# solenoid.net
KiCad netlist of a schematic drawn in Altium Designer
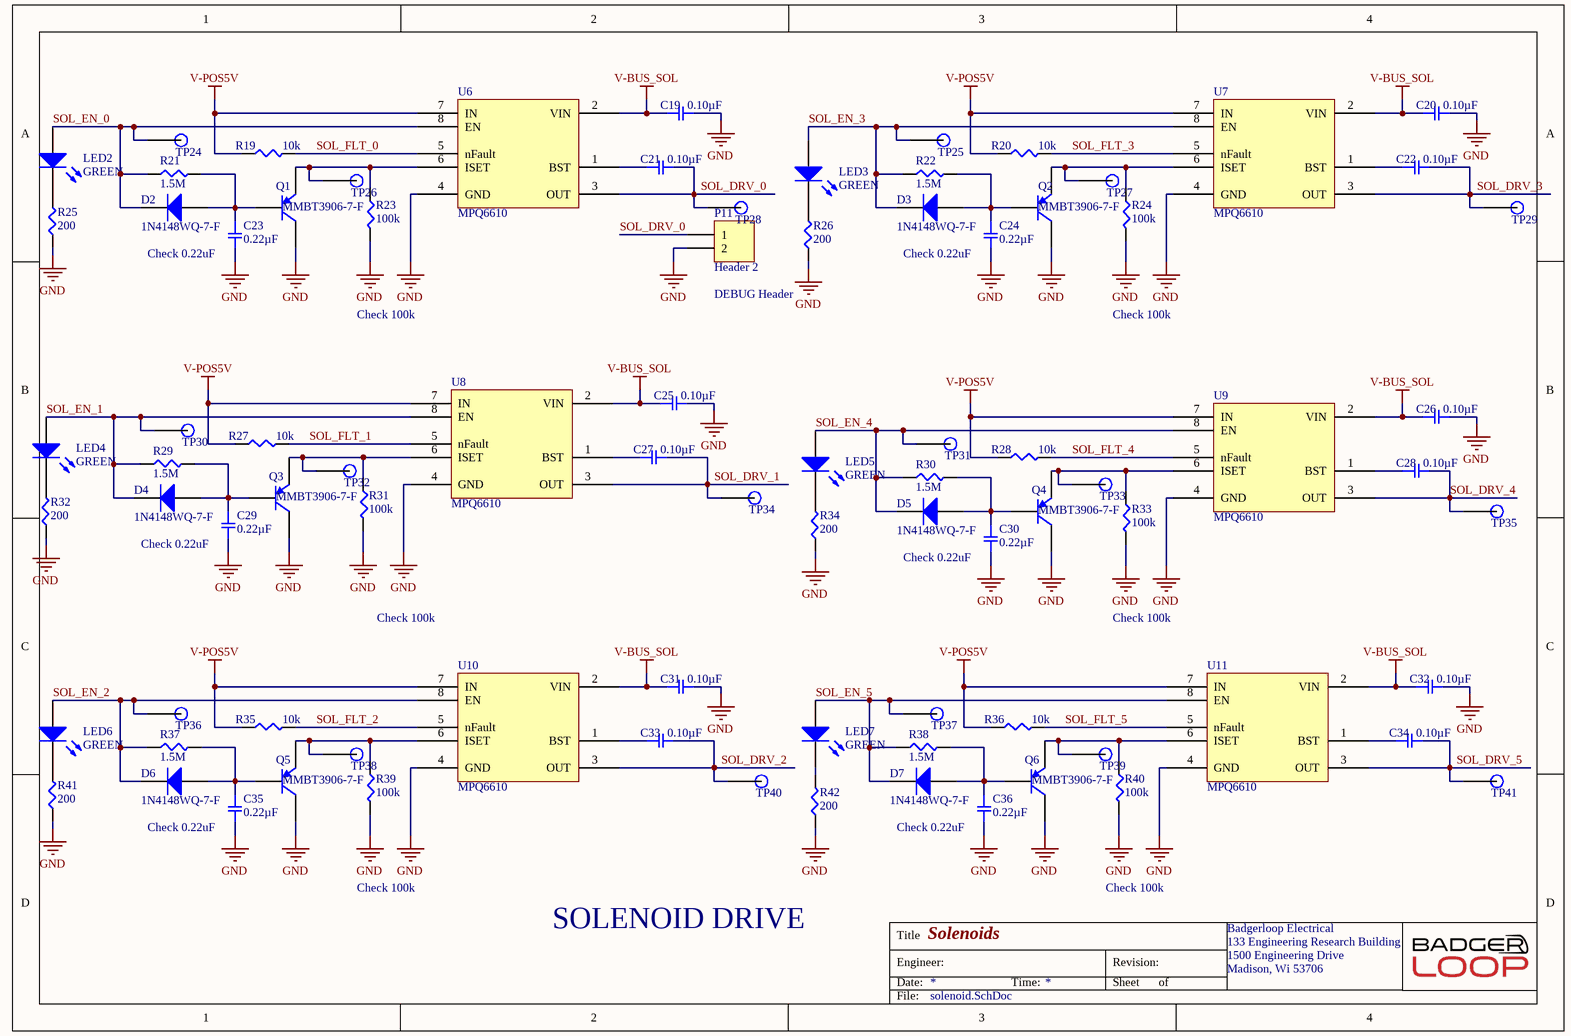
[diagram p0: solenoid.SchDoc]

(export (version "E")
  (design (tool "Eeschema 10.0.6"))
  (components
    (comp (ref "C19")
      (value "0.10µF")
      (footprint "SMD-0805C")
      (description "CAP CER 0.1UF 10V U2J 0805")
      (fields
        (field (name "DIGI-KEY PART NUMBER") "490-11592-1-ND")
        (field (name "PART NUMBER") "GRM21B7U1A104JA01L")
      )
      (libsource (lib "capacitors") (part "GRM21B7U1A104JA01L"))
    )
    (comp (ref "C20")
      (value "0.10µF")
      (footprint "SMD-0805C")
      (description "CAP CER 0.1UF 10V U2J 0805")
      (fields
        (field (name "DIGI-KEY PART NUMBER") "490-11592-1-ND")
        (field (name "PART NUMBER") "GRM21B7U1A104JA01L")
      )
      (libsource (lib "capacitors") (part "GRM21B7U1A104JA01L"))
    )
    (comp (ref "C21")
      (value "0.10µF")
      (footprint "SMD-0805C")
      (description "CAP CER 0.1UF 10V U2J 0805")
      (fields
        (field (name "DIGI-KEY PART NUMBER") "490-11592-1-ND")
        (field (name "PART NUMBER") "GRM21B7U1A104JA01L")
      )
      (libsource (lib "capacitors") (part "GRM21B7U1A104JA01L"))
    )
    (comp (ref "C22")
      (value "0.10µF")
      (footprint "SMD-0805C")
      (description "CAP CER 0.1UF 10V U2J 0805")
      (fields
        (field (name "DIGI-KEY PART NUMBER") "490-11592-1-ND")
        (field (name "PART NUMBER") "GRM21B7U1A104JA01L")
      )
      (libsource (lib "capacitors") (part "GRM21B7U1A104JA01L"))
    )
    (comp (ref "C23")
      (value "0.22µF")
      (footprint "SMD-0805C")
      (description "CAP CER 0.22UF 10V X7R 0805")
      (fields
        (field (name "DIGI-KEY PART NUMBER") "490-4432-1-ND")
        (field (name "PART NUMBER") "LLA215R71A224MA14L")
      )
      (libsource (lib "capacitors") (part "LLA215R71A224MA14L"))
    )
    (comp (ref "C24")
      (value "0.22µF")
      (footprint "SMD-0805C")
      (description "CAP CER 0.22UF 10V X7R 0805")
      (fields
        (field (name "DIGI-KEY PART NUMBER") "490-4432-1-ND")
        (field (name "PART NUMBER") "LLA215R71A224MA14L")
      )
      (libsource (lib "capacitors") (part "LLA215R71A224MA14L"))
    )
    (comp (ref "C25")
      (value "0.10µF")
      (footprint "SMD-0805C")
      (description "CAP CER 0.1UF 10V U2J 0805")
      (fields
        (field (name "DIGI-KEY PART NUMBER") "490-11592-1-ND")
        (field (name "PART NUMBER") "GRM21B7U1A104JA01L")
      )
      (libsource (lib "capacitors") (part "GRM21B7U1A104JA01L"))
    )
    (comp (ref "C26")
      (value "0.10µF")
      (footprint "SMD-0805C")
      (description "CAP CER 0.1UF 10V U2J 0805")
      (fields
        (field (name "DIGI-KEY PART NUMBER") "490-11592-1-ND")
        (field (name "PART NUMBER") "GRM21B7U1A104JA01L")
      )
      (libsource (lib "capacitors") (part "GRM21B7U1A104JA01L"))
    )
    (comp (ref "C27")
      (value "0.10µF")
      (footprint "SMD-0805C")
      (description "CAP CER 0.1UF 10V U2J 0805")
      (fields
        (field (name "DIGI-KEY PART NUMBER") "490-11592-1-ND")
        (field (name "PART NUMBER") "GRM21B7U1A104JA01L")
      )
      (libsource (lib "capacitors") (part "GRM21B7U1A104JA01L"))
    )
    (comp (ref "C28")
      (value "0.10µF")
      (footprint "SMD-0805C")
      (description "CAP CER 0.1UF 10V U2J 0805")
      (fields
        (field (name "DIGI-KEY PART NUMBER") "490-11592-1-ND")
        (field (name "PART NUMBER") "GRM21B7U1A104JA01L")
      )
      (libsource (lib "capacitors") (part "GRM21B7U1A104JA01L"))
    )
    (comp (ref "C29")
      (value "0.22µF")
      (footprint "SMD-0805C")
      (description "CAP CER 0.22UF 10V X7R 0805")
      (fields
        (field (name "DIGI-KEY PART NUMBER") "490-4432-1-ND")
        (field (name "PART NUMBER") "LLA215R71A224MA14L")
      )
      (libsource (lib "capacitors") (part "LLA215R71A224MA14L"))
    )
    (comp (ref "C30")
      (value "0.22µF")
      (footprint "SMD-0805C")
      (description "CAP CER 0.22UF 10V X7R 0805")
      (fields
        (field (name "DIGI-KEY PART NUMBER") "490-4432-1-ND")
        (field (name "PART NUMBER") "LLA215R71A224MA14L")
      )
      (libsource (lib "capacitors") (part "LLA215R71A224MA14L"))
    )
    (comp (ref "C31")
      (value "0.10µF")
      (footprint "SMD-0805C")
      (description "CAP CER 0.1UF 10V U2J 0805")
      (fields
        (field (name "DIGI-KEY PART NUMBER") "490-11592-1-ND")
        (field (name "PART NUMBER") "GRM21B7U1A104JA01L")
      )
      (libsource (lib "capacitors") (part "GRM21B7U1A104JA01L"))
    )
    (comp (ref "C32")
      (value "0.10µF")
      (footprint "SMD-0805C")
      (description "CAP CER 0.1UF 10V U2J 0805")
      (fields
        (field (name "DIGI-KEY PART NUMBER") "490-11592-1-ND")
        (field (name "PART NUMBER") "GRM21B7U1A104JA01L")
      )
      (libsource (lib "capacitors") (part "GRM21B7U1A104JA01L"))
    )
    (comp (ref "C33")
      (value "0.10µF")
      (footprint "SMD-0805C")
      (description "CAP CER 0.1UF 10V U2J 0805")
      (fields
        (field (name "DIGI-KEY PART NUMBER") "490-11592-1-ND")
        (field (name "PART NUMBER") "GRM21B7U1A104JA01L")
      )
      (libsource (lib "capacitors") (part "GRM21B7U1A104JA01L"))
    )
    (comp (ref "C34")
      (value "0.10µF")
      (footprint "SMD-0805C")
      (description "CAP CER 0.1UF 10V U2J 0805")
      (fields
        (field (name "DIGI-KEY PART NUMBER") "490-11592-1-ND")
        (field (name "PART NUMBER") "GRM21B7U1A104JA01L")
      )
      (libsource (lib "capacitors") (part "GRM21B7U1A104JA01L"))
    )
    (comp (ref "C35")
      (value "0.22µF")
      (footprint "SMD-0805C")
      (description "CAP CER 0.22UF 10V X7R 0805")
      (fields
        (field (name "DIGI-KEY PART NUMBER") "490-4432-1-ND")
        (field (name "PART NUMBER") "LLA215R71A224MA14L")
      )
      (libsource (lib "capacitors") (part "LLA215R71A224MA14L"))
    )
    (comp (ref "C36")
      (value "0.22µF")
      (footprint "SMD-0805C")
      (description "CAP CER 0.22UF 10V X7R 0805")
      (fields
        (field (name "DIGI-KEY PART NUMBER") "490-4432-1-ND")
        (field (name "PART NUMBER") "LLA215R71A224MA14L")
      )
      (libsource (lib "capacitors") (part "LLA215R71A224MA14L"))
    )
    (comp (ref "D2")
      (value "1N4148WQ-7-F")
      (footprint "INDM3838X18N")
      (description "Diodes - General Purpose, Power, Switching SMT Fast Switching Diode")
      (fields (field (name "MANUFACTURER") "Diodes Inc."))
      (libsource (lib "misc") (part "1N4148WQ-7-F"))
    )
    (comp (ref "D3")
      (value "1N4148WQ-7-F")
      (footprint "INDM3838X18N")
      (description "Diodes - General Purpose, Power, Switching SMT Fast Switching Diode")
      (fields (field (name "MANUFACTURER") "Diodes Inc."))
      (libsource (lib "misc") (part "1N4148WQ-7-F"))
    )
    (comp (ref "D4")
      (value "1N4148WQ-7-F")
      (footprint "INDM3838X18N")
      (description "Diodes - General Purpose, Power, Switching SMT Fast Switching Diode")
      (fields (field (name "MANUFACTURER") "Diodes Inc."))
      (libsource (lib "misc") (part "1N4148WQ-7-F"))
    )
    (comp (ref "D5")
      (value "1N4148WQ-7-F")
      (footprint "INDM3838X18N")
      (description "Diodes - General Purpose, Power, Switching SMT Fast Switching Diode")
      (fields (field (name "MANUFACTURER") "Diodes Inc."))
      (libsource (lib "misc") (part "1N4148WQ-7-F"))
    )
    (comp (ref "D6")
      (value "1N4148WQ-7-F")
      (footprint "INDM3838X18N")
      (description "Diodes - General Purpose, Power, Switching SMT Fast Switching Diode")
      (fields (field (name "MANUFACTURER") "Diodes Inc."))
      (libsource (lib "misc") (part "1N4148WQ-7-F"))
    )
    (comp (ref "D7")
      (value "1N4148WQ-7-F")
      (footprint "INDM3838X18N")
      (description "Diodes - General Purpose, Power, Switching SMT Fast Switching Diode")
      (fields (field (name "MANUFACTURER") "Diodes Inc."))
      (libsource (lib "misc") (part "1N4148WQ-7-F"))
    )
    (comp (ref "LED2")
      (value "GREEN")
      (footprint "LED 0603 GREEN")
      (fields (field (name "MANUFACTURER") "Lite-On Inc."))
      (libsource (lib "misc") (part "LED GREEN 0603"))
    )
    (comp (ref "LED3")
      (value "GREEN")
      (footprint "LED 0603 GREEN")
      (fields (field (name "MANUFACTURER") "Lite-On Inc."))
      (libsource (lib "misc") (part "LED GREEN 0603"))
    )
    (comp (ref "LED4")
      (value "GREEN")
      (footprint "LED 0603 GREEN")
      (fields (field (name "MANUFACTURER") "Lite-On Inc."))
      (libsource (lib "misc") (part "LED GREEN 0603"))
    )
    (comp (ref "LED5")
      (value "GREEN")
      (footprint "LED 0603 GREEN")
      (fields (field (name "MANUFACTURER") "Lite-On Inc."))
      (libsource (lib "misc") (part "LED GREEN 0603"))
    )
    (comp (ref "LED6")
      (value "GREEN")
      (footprint "LED 0603 GREEN")
      (fields (field (name "MANUFACTURER") "Lite-On Inc."))
      (libsource (lib "misc") (part "LED GREEN 0603"))
    )
    (comp (ref "LED7")
      (value "GREEN")
      (footprint "LED 0603 GREEN")
      (fields (field (name "MANUFACTURER") "Lite-On Inc."))
      (libsource (lib "misc") (part "LED GREEN 0603"))
    )
    (comp (ref "P11")
      (value "Header 2")
      (footprint "Pin Header 1x2 TH Pitch 2.54mm")
      (description "Header, 2-Pin")
      (fields (field (name "PUBLISHER") "Altium Limited"))
      (libsource (lib "connector") (part "Header 2"))
    )
    (comp (ref "Q1")
      (value "MMBT3906-7-F")
      (footprint "SOTFL103P240X110-3N")
      (fields (field (name "MANUFACTURER") "Diodes Zetex"))
      (libsource (lib "misc") (part "MMBT3906-7-F"))
    )
    (comp (ref "Q2")
      (value "MMBT3906-7-F")
      (footprint "SOTFL103P240X110-3N")
      (fields (field (name "MANUFACTURER") "Diodes Zetex"))
      (libsource (lib "misc") (part "MMBT3906-7-F"))
    )
    (comp (ref "Q3")
      (value "MMBT3906-7-F")
      (footprint "SOTFL103P240X110-3N")
      (fields (field (name "MANUFACTURER") "Diodes Zetex"))
      (libsource (lib "misc") (part "MMBT3906-7-F"))
    )
    (comp (ref "Q4")
      (value "MMBT3906-7-F")
      (footprint "SOTFL103P240X110-3N")
      (fields (field (name "MANUFACTURER") "Diodes Zetex"))
      (libsource (lib "misc") (part "MMBT3906-7-F"))
    )
    (comp (ref "Q5")
      (value "MMBT3906-7-F")
      (footprint "SOTFL103P240X110-3N")
      (fields (field (name "MANUFACTURER") "Diodes Zetex"))
      (libsource (lib "misc") (part "MMBT3906-7-F"))
    )
    (comp (ref "Q6")
      (value "MMBT3906-7-F")
      (footprint "SOTFL103P240X110-3N")
      (fields (field (name "MANUFACTURER") "Diodes Zetex"))
      (libsource (lib "misc") (part "MMBT3906-7-F"))
    )
    (comp (ref "R19")
      (value "10k")
      (footprint "SMD-0805-RES")
      (description "RES SMD 10K OHM 5% 1/2W 0805")
      (fields (field (name "PART NUMBER") "ERJ-P06J103V") (field (name "DIGI-KEY PART NUMBER") "P10KADCT-ND"))
      (libsource (lib "resistors") (part "ERJ-P06J103V"))
    )
    (comp (ref "R20")
      (value "10k")
      (footprint "SMD-0805-RES")
      (description "RES SMD 10K OHM 5% 1/2W 0805")
      (fields (field (name "PART NUMBER") "ERJ-P06J103V") (field (name "DIGI-KEY PART NUMBER") "P10KADCT-ND"))
      (libsource (lib "resistors") (part "ERJ-P06J103V"))
    )
    (comp (ref "R21")
      (value "1.5M")
      (footprint "SMD-0805-RES")
      (description "RES SMD 1.5M OHM 5% 1/8W 0805")
      (fields
        (field (name "PART NUMBER") "ERJ-6GEYJ155V")
        (field (name "DIGI-KEY PART NUMBER") "P1.5MACT-ND")
      )
      (libsource (lib "resistors") (part "ERJ-6GEYJ155V"))
    )
    (comp (ref "R22")
      (value "1.5M")
      (footprint "SMD-0805-RES")
      (description "RES SMD 1.5M OHM 5% 1/8W 0805")
      (fields
        (field (name "PART NUMBER") "ERJ-6GEYJ155V")
        (field (name "DIGI-KEY PART NUMBER") "P1.5MACT-ND")
      )
      (libsource (lib "resistors") (part "ERJ-6GEYJ155V"))
    )
    (comp (ref "R23")
      (value "100k")
      (footprint "SMD-0805-RES")
      (description "RES SMD 100K OHM 5% 1/2W 0805")
      (fields
        (field (name "PART NUMBER") "ERJ-P06J104V")
        (field (name "DIGI-KEY PART NUMBER") "P100KADCT-ND")
      )
      (libsource (lib "resistors") (part "ERJ-P06J104V"))
    )
    (comp (ref "R24")
      (value "100k")
      (footprint "SMD-0805-RES")
      (description "RES SMD 100K OHM 5% 1/2W 0805")
      (fields
        (field (name "PART NUMBER") "ERJ-P06J104V")
        (field (name "DIGI-KEY PART NUMBER") "P100KADCT-ND")
      )
      (libsource (lib "resistors") (part "ERJ-P06J104V"))
    )
    (comp (ref "R25")
      (value "200")
      (footprint "SMD-0805-RES")
      (description "RES SMD 200 OHM 1% 1/2W 0805")
      (fields
        (field (name "PART NUMBER") "ERJ-P06F2000V")
        (field (name "DIGI-KEY PART NUMBER") "P16064CT-ND")
      )
      (libsource (lib "resistors") (part "ERJ-P06F2000V"))
    )
    (comp (ref "R26")
      (value "200")
      (footprint "SMD-0805-RES")
      (description "RES SMD 200 OHM 1% 1/2W 0805")
      (fields
        (field (name "PART NUMBER") "ERJ-P06F2000V")
        (field (name "DIGI-KEY PART NUMBER") "P16064CT-ND")
      )
      (libsource (lib "resistors") (part "ERJ-P06F2000V"))
    )
    (comp (ref "R27")
      (value "10k")
      (footprint "SMD-0805-RES")
      (description "RES SMD 10K OHM 5% 1/2W 0805")
      (fields (field (name "PART NUMBER") "ERJ-P06J103V") (field (name "DIGI-KEY PART NUMBER") "P10KADCT-ND"))
      (libsource (lib "resistors") (part "ERJ-P06J103V"))
    )
    (comp (ref "R28")
      (value "10k")
      (footprint "SMD-0805-RES")
      (description "RES SMD 10K OHM 5% 1/2W 0805")
      (fields (field (name "PART NUMBER") "ERJ-P06J103V") (field (name "DIGI-KEY PART NUMBER") "P10KADCT-ND"))
      (libsource (lib "resistors") (part "ERJ-P06J103V"))
    )
    (comp (ref "R29")
      (value "1.5M")
      (footprint "SMD-0805-RES")
      (description "RES SMD 1.5M OHM 5% 1/8W 0805")
      (fields
        (field (name "PART NUMBER") "ERJ-6GEYJ155V")
        (field (name "DIGI-KEY PART NUMBER") "P1.5MACT-ND")
      )
      (libsource (lib "resistors") (part "ERJ-6GEYJ155V"))
    )
    (comp (ref "R30")
      (value "1.5M")
      (footprint "SMD-0805-RES")
      (description "RES SMD 1.5M OHM 5% 1/8W 0805")
      (fields
        (field (name "PART NUMBER") "ERJ-6GEYJ155V")
        (field (name "DIGI-KEY PART NUMBER") "P1.5MACT-ND")
      )
      (libsource (lib "resistors") (part "ERJ-6GEYJ155V"))
    )
    (comp (ref "R31")
      (value "100k")
      (footprint "SMD-0805-RES")
      (description "RES SMD 100K OHM 5% 1/2W 0805")
      (fields
        (field (name "PART NUMBER") "ERJ-P06J104V")
        (field (name "DIGI-KEY PART NUMBER") "P100KADCT-ND")
      )
      (libsource (lib "resistors") (part "ERJ-P06J104V"))
    )
    (comp (ref "R32")
      (value "200")
      (footprint "SMD-0805-RES")
      (description "RES SMD 200 OHM 1% 1/2W 0805")
      (fields
        (field (name "PART NUMBER") "ERJ-P06F2000V")
        (field (name "DIGI-KEY PART NUMBER") "P16064CT-ND")
      )
      (libsource (lib "resistors") (part "ERJ-P06F2000V"))
    )
    (comp (ref "R33")
      (value "100k")
      (footprint "SMD-0805-RES")
      (description "RES SMD 100K OHM 5% 1/2W 0805")
      (fields
        (field (name "PART NUMBER") "ERJ-P06J104V")
        (field (name "DIGI-KEY PART NUMBER") "P100KADCT-ND")
      )
      (libsource (lib "resistors") (part "ERJ-P06J104V"))
    )
    (comp (ref "R34")
      (value "200")
      (footprint "SMD-0805-RES")
      (description "RES SMD 200 OHM 1% 1/2W 0805")
      (fields
        (field (name "PART NUMBER") "ERJ-P06F2000V")
        (field (name "DIGI-KEY PART NUMBER") "P16064CT-ND")
      )
      (libsource (lib "resistors") (part "ERJ-P06F2000V"))
    )
    (comp (ref "R35")
      (value "10k")
      (footprint "SMD-0805-RES")
      (description "RES SMD 10K OHM 5% 1/2W 0805")
      (fields (field (name "PART NUMBER") "ERJ-P06J103V") (field (name "DIGI-KEY PART NUMBER") "P10KADCT-ND"))
      (libsource (lib "resistors") (part "ERJ-P06J103V"))
    )
    (comp (ref "R36")
      (value "10k")
      (footprint "SMD-0805-RES")
      (description "RES SMD 10K OHM 5% 1/2W 0805")
      (fields (field (name "PART NUMBER") "ERJ-P06J103V") (field (name "DIGI-KEY PART NUMBER") "P10KADCT-ND"))
      (libsource (lib "resistors") (part "ERJ-P06J103V"))
    )
    (comp (ref "R37")
      (value "1.5M")
      (footprint "SMD-0805-RES")
      (description "RES SMD 1.5M OHM 5% 1/8W 0805")
      (fields
        (field (name "PART NUMBER") "ERJ-6GEYJ155V")
        (field (name "DIGI-KEY PART NUMBER") "P1.5MACT-ND")
      )
      (libsource (lib "resistors") (part "ERJ-6GEYJ155V"))
    )
    (comp (ref "R38")
      (value "1.5M")
      (footprint "SMD-0805-RES")
      (description "RES SMD 1.5M OHM 5% 1/8W 0805")
      (fields
        (field (name "PART NUMBER") "ERJ-6GEYJ155V")
        (field (name "DIGI-KEY PART NUMBER") "P1.5MACT-ND")
      )
      (libsource (lib "resistors") (part "ERJ-6GEYJ155V"))
    )
    (comp (ref "R39")
      (value "100k")
      (footprint "SMD-0805-RES")
      (description "RES SMD 100K OHM 5% 1/2W 0805")
      (fields
        (field (name "PART NUMBER") "ERJ-P06J104V")
        (field (name "DIGI-KEY PART NUMBER") "P100KADCT-ND")
      )
      (libsource (lib "resistors") (part "ERJ-P06J104V"))
    )
    (comp (ref "R40")
      (value "100k")
      (footprint "SMD-0805-RES")
      (description "RES SMD 100K OHM 5% 1/2W 0805")
      (fields
        (field (name "PART NUMBER") "ERJ-P06J104V")
        (field (name "DIGI-KEY PART NUMBER") "P100KADCT-ND")
      )
      (libsource (lib "resistors") (part "ERJ-P06J104V"))
    )
    (comp (ref "R41")
      (value "200")
      (footprint "SMD-0805-RES")
      (description "RES SMD 200 OHM 1% 1/2W 0805")
      (fields
        (field (name "PART NUMBER") "ERJ-P06F2000V")
        (field (name "DIGI-KEY PART NUMBER") "P16064CT-ND")
      )
      (libsource (lib "resistors") (part "ERJ-P06F2000V"))
    )
    (comp (ref "R42")
      (value "200")
      (footprint "SMD-0805-RES")
      (description "RES SMD 200 OHM 1% 1/2W 0805")
      (fields
        (field (name "PART NUMBER") "ERJ-P06F2000V")
        (field (name "DIGI-KEY PART NUMBER") "P16064CT-ND")
      )
      (libsource (lib "resistors") (part "ERJ-P06F2000V"))
    )
    (comp (ref "TP24")
      (value "TP")
      (footprint "Test Point")
      (description "SMD TEST POINT")
      (libsource (lib "misc") (part "TP"))
    )
    (comp (ref "TP25")
      (value "TP")
      (footprint "Test Point")
      (description "SMD TEST POINT")
      (libsource (lib "misc") (part "TP"))
    )
    (comp (ref "TP26")
      (value "TP")
      (footprint "Test Point")
      (description "SMD TEST POINT")
      (libsource (lib "misc") (part "TP"))
    )
    (comp (ref "TP27")
      (value "TP")
      (footprint "Test Point")
      (description "SMD TEST POINT")
      (libsource (lib "misc") (part "TP"))
    )
    (comp (ref "TP28")
      (value "TP")
      (footprint "Test Point")
      (description "SMD TEST POINT")
      (libsource (lib "misc") (part "TP"))
    )
    (comp (ref "TP29")
      (value "TP")
      (footprint "Test Point")
      (description "SMD TEST POINT")
      (libsource (lib "misc") (part "TP"))
    )
    (comp (ref "TP30")
      (value "TP")
      (footprint "Test Point")
      (description "SMD TEST POINT")
      (libsource (lib "misc") (part "TP"))
    )
    (comp (ref "TP31")
      (value "TP")
      (footprint "Test Point")
      (description "SMD TEST POINT")
      (libsource (lib "misc") (part "TP"))
    )
    (comp (ref "TP32")
      (value "TP")
      (footprint "Test Point")
      (description "SMD TEST POINT")
      (libsource (lib "misc") (part "TP"))
    )
    (comp (ref "TP33")
      (value "TP")
      (footprint "Test Point")
      (description "SMD TEST POINT")
      (libsource (lib "misc") (part "TP"))
    )
    (comp (ref "TP34")
      (value "TP")
      (footprint "Test Point")
      (description "SMD TEST POINT")
      (libsource (lib "misc") (part "TP"))
    )
    (comp (ref "TP35")
      (value "TP")
      (footprint "Test Point")
      (description "SMD TEST POINT")
      (libsource (lib "misc") (part "TP"))
    )
    (comp (ref "TP36")
      (value "TP")
      (footprint "Test Point")
      (description "SMD TEST POINT")
      (libsource (lib "misc") (part "TP"))
    )
    (comp (ref "TP37")
      (value "TP")
      (footprint "Test Point")
      (description "SMD TEST POINT")
      (libsource (lib "misc") (part "TP"))
    )
    (comp (ref "TP38")
      (value "TP")
      (footprint "Test Point")
      (description "SMD TEST POINT")
      (libsource (lib "misc") (part "TP"))
    )
    (comp (ref "TP39")
      (value "TP")
      (footprint "Test Point")
      (description "SMD TEST POINT")
      (libsource (lib "misc") (part "TP"))
    )
    (comp (ref "TP40")
      (value "TP")
      (footprint "Test Point")
      (description "SMD TEST POINT")
      (libsource (lib "misc") (part "TP"))
    )
    (comp (ref "TP41")
      (value "TP")
      (footprint "Test Point")
      (description "SMD TEST POINT")
      (libsource (lib "misc") (part "TP"))
    )
    (comp (ref "U6")
      (value "MPQ6610")
      (footprint "SOP127P600X175-8N")
      (libsource (lib "ic") (part "MPQ6610"))
    )
    (comp (ref "U7")
      (value "MPQ6610")
      (footprint "SOP127P600X175-8N")
      (libsource (lib "ic") (part "MPQ6610"))
    )
    (comp (ref "U8")
      (value "MPQ6610")
      (footprint "SOP127P600X175-8N")
      (libsource (lib "ic") (part "MPQ6610"))
    )
    (comp (ref "U9")
      (value "MPQ6610")
      (footprint "SOP127P600X175-8N")
      (libsource (lib "ic") (part "MPQ6610"))
    )
    (comp (ref "U10")
      (value "MPQ6610")
      (footprint "SOP127P600X175-8N")
      (libsource (lib "ic") (part "MPQ6610"))
    )
    (comp (ref "U11")
      (value "MPQ6610")
      (footprint "SOP127P600X175-8N")
      (libsource (lib "ic") (part "MPQ6610"))
    )
  )
  (nets
    (net (code "1") (name "/SOL_DRV_0") (class "Default")
      (node (ref "C21") (pin "2") (pinfunction "2_2") (pintype "passive"))
      (node (ref "P11") (pin "1") (pinfunction "1_1") (pintype "passive"))
      (node (ref "TP28") (pin "1") (pinfunction "1_1") (pintype "passive"))
      (node (ref "U6") (pin "3") (pinfunction "OUT_3") (pintype "passive"))
    )
    (net (code "2") (name "/SOL_DRV_1") (class "Default")
      (node (ref "C27") (pin "2") (pinfunction "2_2") (pintype "passive"))
      (node (ref "TP34") (pin "1") (pinfunction "1_1") (pintype "passive"))
      (node (ref "U8") (pin "3") (pinfunction "OUT_3") (pintype "passive"))
    )
    (net (code "3") (name "/SOL_DRV_2") (class "Default")
      (node (ref "C33") (pin "2") (pinfunction "2_2") (pintype "passive"))
      (node (ref "TP40") (pin "1") (pinfunction "1_1") (pintype "passive"))
      (node (ref "U10") (pin "3") (pinfunction "OUT_3") (pintype "passive"))
    )
    (net (code "4") (name "/SOL_DRV_3") (class "Default")
      (node (ref "C22") (pin "2") (pinfunction "2_2") (pintype "passive"))
      (node (ref "TP29") (pin "1") (pinfunction "1_1") (pintype "passive"))
      (node (ref "U7") (pin "3") (pinfunction "OUT_3") (pintype "passive"))
    )
    (net (code "5") (name "/SOL_DRV_4") (class "Default")
      (node (ref "C28") (pin "2") (pinfunction "2_2") (pintype "passive"))
      (node (ref "TP35") (pin "1") (pinfunction "1_1") (pintype "passive"))
      (node (ref "U9") (pin "3") (pinfunction "OUT_3") (pintype "passive"))
    )
    (net (code "6") (name "/SOL_DRV_5") (class "Default")
      (node (ref "C34") (pin "2") (pinfunction "2_2") (pintype "passive"))
      (node (ref "TP41") (pin "1") (pinfunction "1_1") (pintype "passive"))
      (node (ref "U11") (pin "3") (pinfunction "OUT_3") (pintype "passive"))
    )
    (net (code "7") (name "/SOL_EN_0") (class "Default")
      (node (ref "D2") (pin "2") (pinfunction "K_2") (pintype "passive"))
      (node (ref "LED2") (pin "1") (pinfunction "A_1") (pintype "passive"))
      (node (ref "R21") (pin "1") (pinfunction "1_1") (pintype "passive"))
      (node (ref "TP24") (pin "1") (pinfunction "1_1") (pintype "passive"))
      (node (ref "U6") (pin "8") (pinfunction "EN_8") (pintype "power_in"))
    )
    (net (code "8") (name "/SOL_EN_1") (class "Default")
      (node (ref "D4") (pin "2") (pinfunction "K_2") (pintype "passive"))
      (node (ref "LED4") (pin "1") (pinfunction "A_1") (pintype "passive"))
      (node (ref "R29") (pin "1") (pinfunction "1_1") (pintype "passive"))
      (node (ref "TP30") (pin "1") (pinfunction "1_1") (pintype "passive"))
      (node (ref "U8") (pin "8") (pinfunction "EN_8") (pintype "power_in"))
    )
    (net (code "9") (name "/SOL_EN_2") (class "Default")
      (node (ref "D6") (pin "2") (pinfunction "K_2") (pintype "passive"))
      (node (ref "LED6") (pin "1") (pinfunction "A_1") (pintype "passive"))
      (node (ref "R37") (pin "1") (pinfunction "1_1") (pintype "passive"))
      (node (ref "TP36") (pin "1") (pinfunction "1_1") (pintype "passive"))
      (node (ref "U10") (pin "8") (pinfunction "EN_8") (pintype "power_in"))
    )
    (net (code "10") (name "/SOL_EN_3") (class "Default")
      (node (ref "D3") (pin "2") (pinfunction "K_2") (pintype "passive"))
      (node (ref "LED3") (pin "1") (pinfunction "A_1") (pintype "passive"))
      (node (ref "R22") (pin "1") (pinfunction "1_1") (pintype "passive"))
      (node (ref "TP25") (pin "1") (pinfunction "1_1") (pintype "passive"))
      (node (ref "U7") (pin "8") (pinfunction "EN_8") (pintype "power_in"))
    )
    (net (code "11") (name "/SOL_EN_4") (class "Default")
      (node (ref "D5") (pin "2") (pinfunction "K_2") (pintype "passive"))
      (node (ref "LED5") (pin "1") (pinfunction "A_1") (pintype "passive"))
      (node (ref "R30") (pin "1") (pinfunction "1_1") (pintype "passive"))
      (node (ref "TP31") (pin "1") (pinfunction "1_1") (pintype "passive"))
      (node (ref "U9") (pin "8") (pinfunction "EN_8") (pintype "power_in"))
    )
    (net (code "12") (name "/SOL_EN_5") (class "Default")
      (node (ref "D7") (pin "2") (pinfunction "K_2") (pintype "passive"))
      (node (ref "LED7") (pin "1") (pinfunction "A_1") (pintype "passive"))
      (node (ref "R38") (pin "1") (pinfunction "1_1") (pintype "passive"))
      (node (ref "TP37") (pin "1") (pinfunction "1_1") (pintype "passive"))
      (node (ref "U11") (pin "8") (pinfunction "EN_8") (pintype "power_in"))
    )
    (net (code "13") (name "/SOL_FLT_0") (class "Default")
      (node (ref "R19") (pin "2") (pinfunction "2_2") (pintype "passive"))
      (node (ref "U6") (pin "5") (pinfunction "nFault_5") (pintype "passive"))
    )
    (net (code "14") (name "/SOL_FLT_1") (class "Default")
      (node (ref "R27") (pin "2") (pinfunction "2_2") (pintype "passive"))
      (node (ref "U8") (pin "5") (pinfunction "nFault_5") (pintype "passive"))
    )
    (net (code "15") (name "/SOL_FLT_2") (class "Default")
      (node (ref "R35") (pin "2") (pinfunction "2_2") (pintype "passive"))
      (node (ref "U10") (pin "5") (pinfunction "nFault_5") (pintype "passive"))
    )
    (net (code "16") (name "/SOL_FLT_3") (class "Default")
      (node (ref "R20") (pin "2") (pinfunction "2_2") (pintype "passive"))
      (node (ref "U7") (pin "5") (pinfunction "nFault_5") (pintype "passive"))
    )
    (net (code "17") (name "/SOL_FLT_4") (class "Default")
      (node (ref "R28") (pin "2") (pinfunction "2_2") (pintype "passive"))
      (node (ref "U9") (pin "5") (pinfunction "nFault_5") (pintype "passive"))
    )
    (net (code "18") (name "/SOL_FLT_5") (class "Default")
      (node (ref "R36") (pin "2") (pinfunction "2_2") (pintype "passive"))
      (node (ref "U11") (pin "5") (pinfunction "nFault_5") (pintype "passive"))
    )
    (net (code "19") (name "GND") (class "Default")
      (node (ref "C19") (pin "2") (pinfunction "2_2") (pintype "passive"))
      (node (ref "C20") (pin "2") (pinfunction "2_2") (pintype "passive"))
      (node (ref "C23") (pin "2") (pinfunction "2_2") (pintype "passive"))
      (node (ref "C24") (pin "2") (pinfunction "2_2") (pintype "passive"))
      (node (ref "C25") (pin "2") (pinfunction "2_2") (pintype "passive"))
      (node (ref "C26") (pin "2") (pinfunction "2_2") (pintype "passive"))
      (node (ref "C29") (pin "2") (pinfunction "2_2") (pintype "passive"))
      (node (ref "C30") (pin "2") (pinfunction "2_2") (pintype "passive"))
      (node (ref "C31") (pin "2") (pinfunction "2_2") (pintype "passive"))
      (node (ref "C32") (pin "2") (pinfunction "2_2") (pintype "passive"))
      (node (ref "C35") (pin "2") (pinfunction "2_2") (pintype "passive"))
      (node (ref "C36") (pin "2") (pinfunction "2_2") (pintype "passive"))
      (node (ref "P11") (pin "2") (pinfunction "2_2") (pintype "passive"))
      (node (ref "Q1") (pin "3") (pinfunction "C_3") (pintype "passive"))
      (node (ref "Q2") (pin "3") (pinfunction "C_3") (pintype "passive"))
      (node (ref "Q3") (pin "3") (pinfunction "C_3") (pintype "passive"))
      (node (ref "Q4") (pin "3") (pinfunction "C_3") (pintype "passive"))
      (node (ref "Q5") (pin "3") (pinfunction "C_3") (pintype "passive"))
      (node (ref "Q6") (pin "3") (pinfunction "C_3") (pintype "passive"))
      (node (ref "R23") (pin "2") (pinfunction "2_2") (pintype "passive"))
      (node (ref "R24") (pin "2") (pinfunction "2_2") (pintype "passive"))
      (node (ref "R25") (pin "1") (pinfunction "1_1") (pintype "passive"))
      (node (ref "R26") (pin "1") (pinfunction "1_1") (pintype "passive"))
      (node (ref "R31") (pin "2") (pinfunction "2_2") (pintype "passive"))
      (node (ref "R32") (pin "1") (pinfunction "1_1") (pintype "passive"))
      (node (ref "R33") (pin "2") (pinfunction "2_2") (pintype "passive"))
      (node (ref "R34") (pin "1") (pinfunction "1_1") (pintype "passive"))
      (node (ref "R39") (pin "2") (pinfunction "2_2") (pintype "passive"))
      (node (ref "R40") (pin "2") (pinfunction "2_2") (pintype "passive"))
      (node (ref "R41") (pin "1") (pinfunction "1_1") (pintype "passive"))
      (node (ref "R42") (pin "1") (pinfunction "1_1") (pintype "passive"))
      (node (ref "U10") (pin "4") (pinfunction "GND_4") (pintype "passive"))
      (node (ref "U11") (pin "4") (pinfunction "GND_4") (pintype "passive"))
      (node (ref "U6") (pin "4") (pinfunction "GND_4") (pintype "passive"))
      (node (ref "U7") (pin "4") (pinfunction "GND_4") (pintype "passive"))
      (node (ref "U8") (pin "4") (pinfunction "GND_4") (pintype "passive"))
      (node (ref "U9") (pin "4") (pinfunction "GND_4") (pintype "passive"))
    )
    (net (code "20") (name "Net-(D2-A)") (class "Default")
      (node (ref "C23") (pin "1") (pinfunction "1_1") (pintype "passive"))
      (node (ref "D2") (pin "1") (pinfunction "A_1") (pintype "passive"))
      (node (ref "Q1") (pin "1") (pinfunction "B_1") (pintype "passive"))
      (node (ref "R21") (pin "2") (pinfunction "2_2") (pintype "passive"))
    )
    (net (code "21") (name "Net-(D3-A)") (class "Default")
      (node (ref "C24") (pin "1") (pinfunction "1_1") (pintype "passive"))
      (node (ref "D3") (pin "1") (pinfunction "A_1") (pintype "passive"))
      (node (ref "Q2") (pin "1") (pinfunction "B_1") (pintype "passive"))
      (node (ref "R22") (pin "2") (pinfunction "2_2") (pintype "passive"))
    )
    (net (code "22") (name "Net-(D4-A)") (class "Default")
      (node (ref "C29") (pin "1") (pinfunction "1_1") (pintype "passive"))
      (node (ref "D4") (pin "1") (pinfunction "A_1") (pintype "passive"))
      (node (ref "Q3") (pin "1") (pinfunction "B_1") (pintype "passive"))
      (node (ref "R29") (pin "2") (pinfunction "2_2") (pintype "passive"))
    )
    (net (code "23") (name "Net-(D5-A)") (class "Default")
      (node (ref "C30") (pin "1") (pinfunction "1_1") (pintype "passive"))
      (node (ref "D5") (pin "1") (pinfunction "A_1") (pintype "passive"))
      (node (ref "Q4") (pin "1") (pinfunction "B_1") (pintype "passive"))
      (node (ref "R30") (pin "2") (pinfunction "2_2") (pintype "passive"))
    )
    (net (code "24") (name "Net-(D6-A)") (class "Default")
      (node (ref "C35") (pin "1") (pinfunction "1_1") (pintype "passive"))
      (node (ref "D6") (pin "1") (pinfunction "A_1") (pintype "passive"))
      (node (ref "Q5") (pin "1") (pinfunction "B_1") (pintype "passive"))
      (node (ref "R37") (pin "2") (pinfunction "2_2") (pintype "passive"))
    )
    (net (code "25") (name "Net-(D7-A)") (class "Default")
      (node (ref "C36") (pin "1") (pinfunction "1_1") (pintype "passive"))
      (node (ref "D7") (pin "1") (pinfunction "A_1") (pintype "passive"))
      (node (ref "Q6") (pin "1") (pinfunction "B_1") (pintype "passive"))
      (node (ref "R38") (pin "2") (pinfunction "2_2") (pintype "passive"))
    )
    (net (code "26") (name "Net-(LED2-K)") (class "Default")
      (node (ref "LED2") (pin "2") (pinfunction "K_2") (pintype "passive"))
      (node (ref "R25") (pin "2") (pinfunction "2_2") (pintype "passive"))
    )
    (net (code "27") (name "Net-(LED3-K)") (class "Default")
      (node (ref "LED3") (pin "2") (pinfunction "K_2") (pintype "passive"))
      (node (ref "R26") (pin "2") (pinfunction "2_2") (pintype "passive"))
    )
    (net (code "28") (name "Net-(LED4-K)") (class "Default")
      (node (ref "LED4") (pin "2") (pinfunction "K_2") (pintype "passive"))
      (node (ref "R32") (pin "2") (pinfunction "2_2") (pintype "passive"))
    )
    (net (code "29") (name "Net-(LED5-K)") (class "Default")
      (node (ref "LED5") (pin "2") (pinfunction "K_2") (pintype "passive"))
      (node (ref "R34") (pin "2") (pinfunction "2_2") (pintype "passive"))
    )
    (net (code "30") (name "Net-(LED6-K)") (class "Default")
      (node (ref "LED6") (pin "2") (pinfunction "K_2") (pintype "passive"))
      (node (ref "R41") (pin "2") (pinfunction "2_2") (pintype "passive"))
    )
    (net (code "31") (name "Net-(LED7-K)") (class "Default")
      (node (ref "LED7") (pin "2") (pinfunction "K_2") (pintype "passive"))
      (node (ref "R42") (pin "2") (pinfunction "2_2") (pintype "passive"))
    )
    (net (code "32") (name "Net-(Q1-E)") (class "Default")
      (node (ref "Q1") (pin "2") (pinfunction "E_2") (pintype "passive"))
      (node (ref "R23") (pin "1") (pinfunction "1_1") (pintype "passive"))
      (node (ref "TP26") (pin "1") (pinfunction "1_1") (pintype "passive"))
      (node (ref "U6") (pin "6") (pinfunction "ISET_6") (pintype "power_in"))
    )
    (net (code "33") (name "Net-(Q2-E)") (class "Default")
      (node (ref "Q2") (pin "2") (pinfunction "E_2") (pintype "passive"))
      (node (ref "R24") (pin "1") (pinfunction "1_1") (pintype "passive"))
      (node (ref "TP27") (pin "1") (pinfunction "1_1") (pintype "passive"))
      (node (ref "U7") (pin "6") (pinfunction "ISET_6") (pintype "power_in"))
    )
    (net (code "34") (name "Net-(Q3-E)") (class "Default")
      (node (ref "Q3") (pin "2") (pinfunction "E_2") (pintype "passive"))
      (node (ref "R31") (pin "1") (pinfunction "1_1") (pintype "passive"))
      (node (ref "TP32") (pin "1") (pinfunction "1_1") (pintype "passive"))
      (node (ref "U8") (pin "6") (pinfunction "ISET_6") (pintype "power_in"))
    )
    (net (code "35") (name "Net-(Q4-E)") (class "Default")
      (node (ref "Q4") (pin "2") (pinfunction "E_2") (pintype "passive"))
      (node (ref "R33") (pin "1") (pinfunction "1_1") (pintype "passive"))
      (node (ref "TP33") (pin "1") (pinfunction "1_1") (pintype "passive"))
      (node (ref "U9") (pin "6") (pinfunction "ISET_6") (pintype "power_in"))
    )
    (net (code "36") (name "Net-(Q5-E)") (class "Default")
      (node (ref "Q5") (pin "2") (pinfunction "E_2") (pintype "passive"))
      (node (ref "R39") (pin "1") (pinfunction "1_1") (pintype "passive"))
      (node (ref "TP38") (pin "1") (pinfunction "1_1") (pintype "passive"))
      (node (ref "U10") (pin "6") (pinfunction "ISET_6") (pintype "power_in"))
    )
    (net (code "37") (name "Net-(Q6-E)") (class "Default")
      (node (ref "Q6") (pin "2") (pinfunction "E_2") (pintype "passive"))
      (node (ref "R40") (pin "1") (pinfunction "1_1") (pintype "passive"))
      (node (ref "TP39") (pin "1") (pinfunction "1_1") (pintype "passive"))
      (node (ref "U11") (pin "6") (pinfunction "ISET_6") (pintype "power_in"))
    )
    (net (code "38") (name "Net-(U6-BST)") (class "Default")
      (node (ref "C21") (pin "1") (pinfunction "1_1") (pintype "passive"))
      (node (ref "U6") (pin "1") (pinfunction "BST_1") (pintype "passive"))
    )
    (net (code "39") (name "Net-(U7-BST)") (class "Default")
      (node (ref "C22") (pin "1") (pinfunction "1_1") (pintype "passive"))
      (node (ref "U7") (pin "1") (pinfunction "BST_1") (pintype "passive"))
    )
    (net (code "40") (name "Net-(U8-BST)") (class "Default")
      (node (ref "C27") (pin "1") (pinfunction "1_1") (pintype "passive"))
      (node (ref "U8") (pin "1") (pinfunction "BST_1") (pintype "passive"))
    )
    (net (code "41") (name "Net-(U9-BST)") (class "Default")
      (node (ref "C28") (pin "1") (pinfunction "1_1") (pintype "passive"))
      (node (ref "U9") (pin "1") (pinfunction "BST_1") (pintype "passive"))
    )
    (net (code "42") (name "Net-(U10-BST)") (class "Default")
      (node (ref "C33") (pin "1") (pinfunction "1_1") (pintype "passive"))
      (node (ref "U10") (pin "1") (pinfunction "BST_1") (pintype "passive"))
    )
    (net (code "43") (name "Net-(U11-BST)") (class "Default")
      (node (ref "C34") (pin "1") (pinfunction "1_1") (pintype "passive"))
      (node (ref "U11") (pin "1") (pinfunction "BST_1") (pintype "passive"))
    )
    (net (code "44") (name "V-BUS_SOL") (class "Default")
      (node (ref "C19") (pin "1") (pinfunction "1_1") (pintype "passive"))
      (node (ref "C20") (pin "1") (pinfunction "1_1") (pintype "passive"))
      (node (ref "C25") (pin "1") (pinfunction "1_1") (pintype "passive"))
      (node (ref "C26") (pin "1") (pinfunction "1_1") (pintype "passive"))
      (node (ref "C31") (pin "1") (pinfunction "1_1") (pintype "passive"))
      (node (ref "C32") (pin "1") (pinfunction "1_1") (pintype "passive"))
      (node (ref "U10") (pin "2") (pinfunction "VIN_2") (pintype "passive"))
      (node (ref "U11") (pin "2") (pinfunction "VIN_2") (pintype "passive"))
      (node (ref "U6") (pin "2") (pinfunction "VIN_2") (pintype "passive"))
      (node (ref "U7") (pin "2") (pinfunction "VIN_2") (pintype "passive"))
      (node (ref "U8") (pin "2") (pinfunction "VIN_2") (pintype "passive"))
      (node (ref "U9") (pin "2") (pinfunction "VIN_2") (pintype "passive"))
    )
    (net (code "45") (name "V-POS5V") (class "Default")
      (node (ref "R19") (pin "1") (pinfunction "1_1") (pintype "passive"))
      (node (ref "R20") (pin "1") (pinfunction "1_1") (pintype "passive"))
      (node (ref "R27") (pin "1") (pinfunction "1_1") (pintype "passive"))
      (node (ref "R28") (pin "1") (pinfunction "1_1") (pintype "passive"))
      (node (ref "R35") (pin "1") (pinfunction "1_1") (pintype "passive"))
      (node (ref "R36") (pin "1") (pinfunction "1_1") (pintype "passive"))
      (node (ref "U10") (pin "7") (pinfunction "IN_7") (pintype "passive"))
      (node (ref "U11") (pin "7") (pinfunction "IN_7") (pintype "passive"))
      (node (ref "U6") (pin "7") (pinfunction "IN_7") (pintype "passive"))
      (node (ref "U7") (pin "7") (pinfunction "IN_7") (pintype "passive"))
      (node (ref "U8") (pin "7") (pinfunction "IN_7") (pintype "passive"))
      (node (ref "U9") (pin "7") (pinfunction "IN_7") (pintype "passive"))
    )
  )
)
